# Test_board_TG21_A_B.net
KiCad netlist of a schematic drawn in Altium Designer
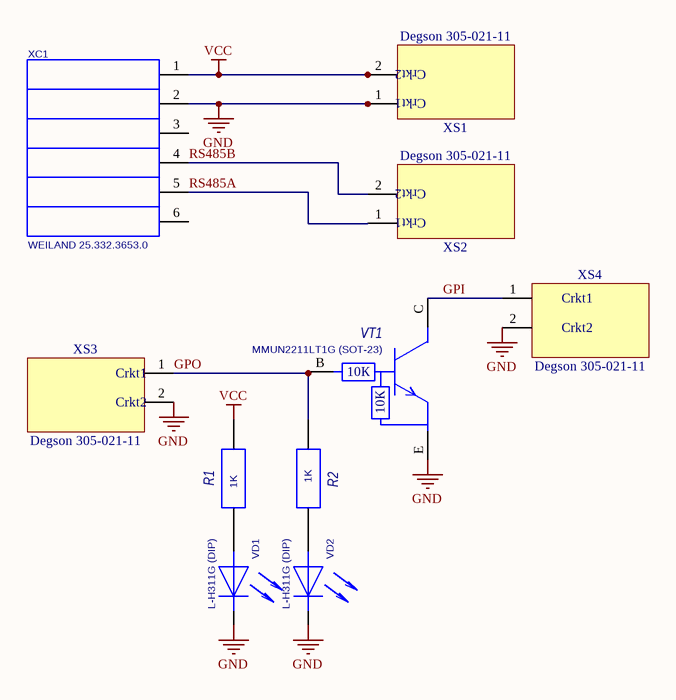
[diagram p0: Test board TG21.A_B.SchDoc]

(export (version "E")
  (design (tool "Eeschema 10.0.6"))
  (components
    (comp (ref "R1")
      (value "1K")
      (footprint "RESC0603N")
      (description "R0603")
      (fields (field (name "MFG") "ф.Bourns"))
      (libsource (lib "pass_smd") (part "R0603"))
    )
    (comp (ref "R2")
      (value "1K")
      (footprint "RESC0603N")
      (description "R0603")
      (fields (field (name "MFG") "ф.Bourns"))
      (libsource (lib "pass_smd") (part "R0603"))
    )
    (comp (ref "VD1")
      (value "L-H311G (DIP)")
      (footprint "L-H311")
      (description "L-H311G")
      (libsource (lib "diodes") (part "L-H311G"))
    )
    (comp (ref "VD2")
      (value "L-H311G (DIP)")
      (footprint "L-H311")
      (description "L-H311G")
      (libsource (lib "diodes") (part "L-H311G"))
    )
    (comp (ref "VT1")
      (value "MMUN2211LT1G (SOT-23)")
      (footprint "SOT95P230-3N (SOT-23)")
      (description "MUN2211T1")
      (fields
        (field (name "CMPPARTNUM") "MMUN2211LT1G")
        (field (name "PARR1VALUE") "10К")
        (field (name "PARR2VALUE") "10К")
      )
      (libsource (lib "transistors") (part "MUN2211T1"))
    )
    (comp (ref "XC1")
      (value "WEILAND 25.332.3653.0")
      (footprint "WEILAND_25.332.3653.0")
      (description "WEILAND_6PIN_5MM")
      (libsource (lib "connectors") (part "WEILAND_6PIN_5MM"))
    )
    (comp (ref "XS1")
      (value "Degson 305-021-11")
      (footprint "305-021-11")
      (description "Клеммник винтовой, 2-контактный, 5мм, прямой")
      (fields (field (name "CMPPARTNUM") "305-021-11"))
      (libsource (lib "connectors") (part "305-021-11"))
    )
    (comp (ref "XS2")
      (value "Degson 305-021-11")
      (footprint "305-021-11")
      (description "Клеммник винтовой, 2-контактный, 5мм, прямой")
      (fields (field (name "CMPPARTNUM") "305-021-11"))
      (libsource (lib "connectors") (part "305-021-11"))
    )
    (comp (ref "XS3")
      (value "Degson 305-021-11")
      (footprint "305-021-11")
      (description "Клеммник винтовой, 2-контактный, 5мм, прямой")
      (fields (field (name "CMPPARTNUM") "305-021-11"))
      (libsource (lib "") (part "305-021-11_1"))
    )
    (comp (ref "XS4")
      (value "Degson 305-021-11")
      (footprint "305-021-11")
      (description "Клеммник винтовой, 2-контактный, 5мм, прямой")
      (fields (field (name "CMPPARTNUM") "305-021-11"))
      (libsource (lib "") (part "305-021-11_2"))
    )
  )
  (nets
    (net (code "1") (name "/GPI") (class "Default")
      (node (ref "VT1") (pin "C") (pinfunction "C_C") (pintype "passive"))
      (node (ref "XS4") (pin "1") (pinfunction "1_1") (pintype "passive"))
    )
    (net (code "2") (name "/GPO") (class "Default")
      (node (ref "R2") (pin "1") (pinfunction "1_1") (pintype "passive"))
      (node (ref "VT1") (pin "B") (pinfunction "B_B") (pintype "passive"))
      (node (ref "XS3") (pin "1") (pinfunction "1_1") (pintype "passive"))
    )
    (net (code "3") (name "/RS485A") (class "Default")
      (node (ref "XC1") (pin "5") (pinfunction "5_5") (pintype "passive"))
      (node (ref "XS2") (pin "1") (pinfunction "1_1") (pintype "passive"))
    )
    (net (code "4") (name "/RS485B") (class "Default")
      (node (ref "XC1") (pin "4") (pinfunction "4_4") (pintype "passive"))
      (node (ref "XS2") (pin "2") (pinfunction "2_2") (pintype "passive"))
    )
    (net (code "5") (name "GND") (class "Default")
      (node (ref "VD1") (pin "2") (pinfunction "cathode_2") (pintype "passive"))
      (node (ref "VD2") (pin "2") (pinfunction "cathode_2") (pintype "passive"))
      (node (ref "VT1") (pin "E") (pinfunction "E_E") (pintype "passive"))
      (node (ref "XC1") (pin "2") (pinfunction "2_2") (pintype "passive"))
      (node (ref "XS1") (pin "1") (pinfunction "1_1") (pintype "passive"))
      (node (ref "XS3") (pin "2") (pinfunction "2_2") (pintype "passive"))
      (node (ref "XS4") (pin "2") (pinfunction "2_2") (pintype "passive"))
    )
    (net (code "6") (name "Net-(VD1-anod)") (class "Default")
      (node (ref "R1") (pin "1") (pinfunction "1_1") (pintype "passive"))
      (node (ref "VD1") (pin "1") (pinfunction "anod_1") (pintype "passive"))
    )
    (net (code "7") (name "Net-(VD2-anod)") (class "Default")
      (node (ref "R2") (pin "2") (pinfunction "2_2") (pintype "passive"))
      (node (ref "VD2") (pin "1") (pinfunction "anod_1") (pintype "passive"))
    )
    (net (code "8") (name "VCC") (class "Default")
      (node (ref "R1") (pin "2") (pinfunction "2_2") (pintype "passive"))
      (node (ref "XC1") (pin "1") (pinfunction "1_1") (pintype "passive"))
      (node (ref "XS1") (pin "2") (pinfunction "2_2") (pintype "passive"))
    )
    (net (code "9") (name "unconnected-(XC1-Pad3)") (class "Default")
      (node (ref "XC1") (pin "3") (pinfunction "3_3") (pintype "passive"))
    )
    (net (code "10") (name "unconnected-(XC1-Pad6)") (class "Default")
      (node (ref "XC1") (pin "6") (pinfunction "6_6") (pintype "passive"))
    )
  )
)
